# Parametrischer_EQ.net
KiCad netlist of a schematic drawn in Altium Designer
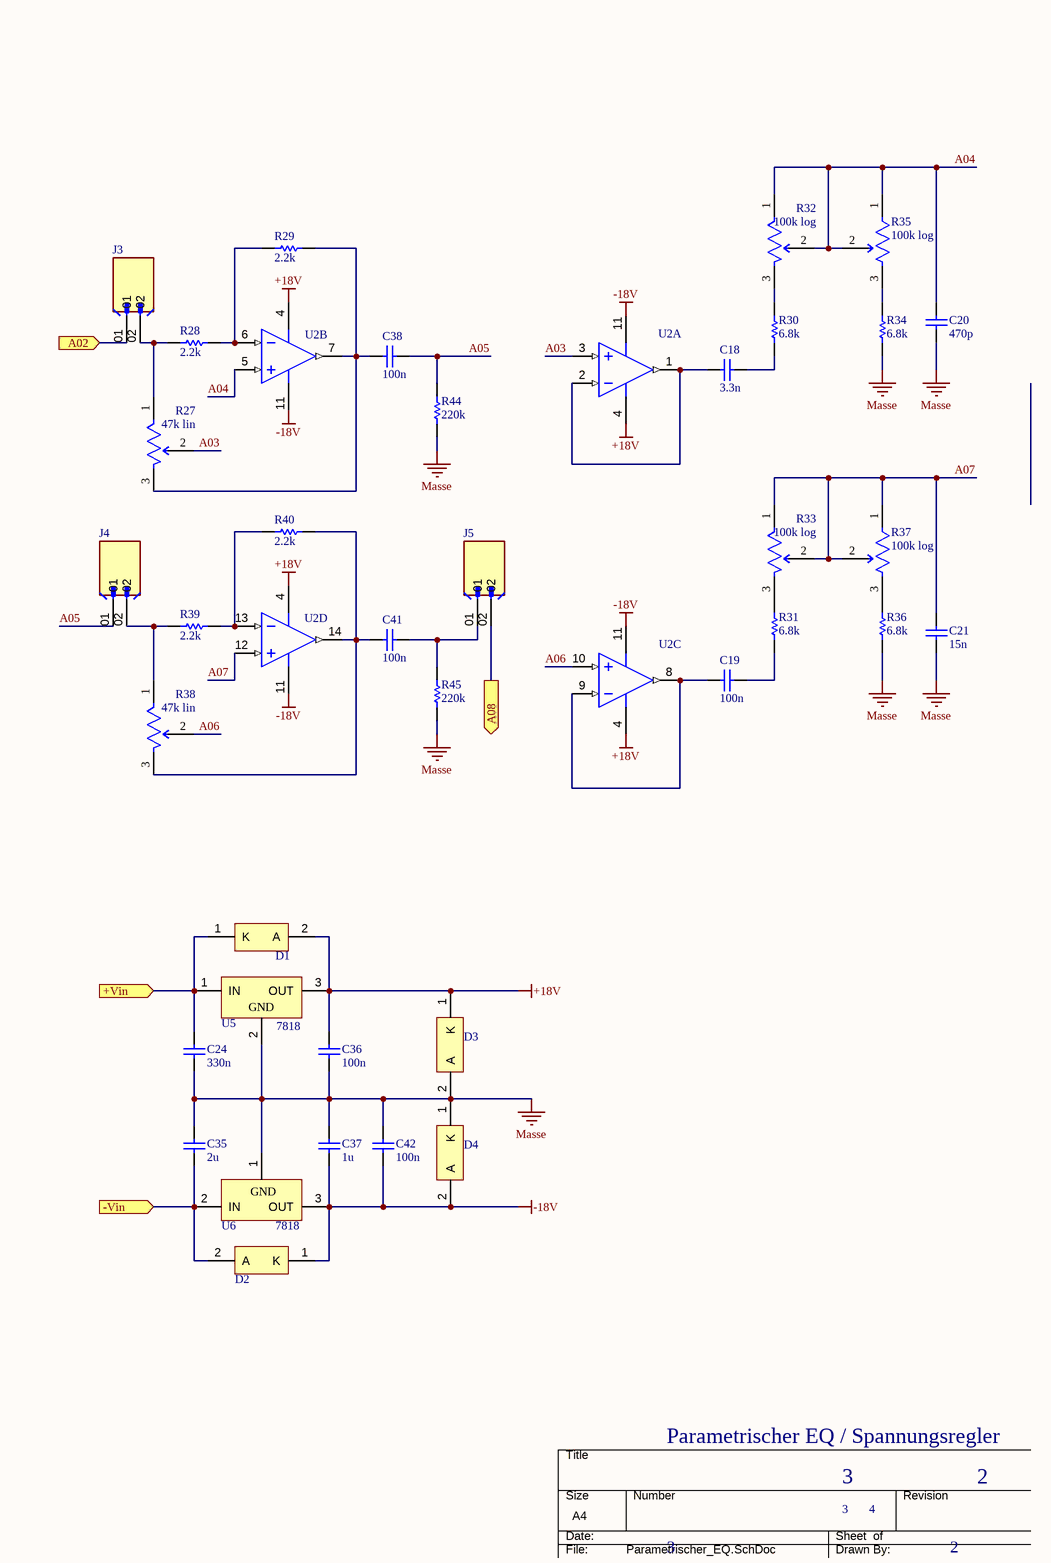
[diagram p0: Parametrischer_EQ.SchDoc]

(export (version "E")
  (design (tool "Eeschema 10.0.6"))
  (components
    (comp (ref "C18")
      (value "3.3n")
      (footprint "0805")
      (description "0805 Kondensator")
      (libsource (lib "Bauteile") (part "0805 Kondensator"))
    )
    (comp (ref "C19")
      (value "100n")
      (footprint "0805")
      (description "0805 Kondensator")
      (libsource (lib "Bauteile") (part "0805 Kondensator"))
    )
    (comp (ref "C20")
      (value "470p")
      (footprint "0805")
      (description "0805 Kondensator")
      (libsource (lib "Bauteile") (part "0805 Kondensator"))
    )
    (comp (ref "C21")
      (value "15n")
      (footprint "0805")
      (description "0805 Kondensator")
      (libsource (lib "Bauteile") (part "0805 Kondensator"))
    )
    (comp (ref "C24")
      (value "330n")
      (footprint "0805")
      (description "0805 Kondensator")
      (libsource (lib "Bauteile") (part "0805 Kondensator"))
    )
    (comp (ref "C35")
      (value "2u")
      (footprint "0805")
      (description "0805 Kondensator")
      (libsource (lib "Bauteile") (part "0805 Kondensator"))
    )
    (comp (ref "C36")
      (value "100n")
      (footprint "0805")
      (description "0805 Kondensator")
      (libsource (lib "Bauteile") (part "0805 Kondensator"))
    )
    (comp (ref "C37")
      (value "1u")
      (footprint "0805")
      (description "0805 Kondensator")
      (libsource (lib "Bauteile") (part "0805 Kondensator"))
    )
    (comp (ref "C38")
      (value "100n")
      (footprint "0805")
      (description "0805 Kondensator")
      (libsource (lib "Bauteile") (part "0805 Kondensator"))
    )
    (comp (ref "C41")
      (value "100n")
      (footprint "0805")
      (description "0805 Kondensator")
      (libsource (lib "Bauteile") (part "0805 Kondensator"))
    )
    (comp (ref "C42")
      (value "100n")
      (footprint "0805")
      (description "0805 Kondensator")
      (libsource (lib "Bauteile") (part "0805 Kondensator"))
    )
    (comp (ref "D1")
      (value "1N4001 Diode")
      (footprint "1N4001 Diode")
      (description "Standard Recovery Rectifier, 2-Pin Axial_Lead, Pb-Free, Bulk Bag")
      (fields (field (name "PARTNUMBER") "1N4001") (field (name "MANUFACTURER") "On Semiconductor"))
      (libsource (lib "") (part "1N4001 Diode_2"))
    )
    (comp (ref "D2")
      (value "1N4001 Diode")
      (footprint "1N4001 Diode")
      (description "Standard Recovery Rectifier, 2-Pin Axial_Lead, Pb-Free, Bulk Bag")
      (fields (field (name "PARTNUMBER") "1N4001") (field (name "MANUFACTURER") "On Semiconductor"))
      (libsource (lib "Bauteile") (part "1N4001 Diode"))
    )
    (comp (ref "D3")
      (value "1N4001 Diode")
      (footprint "1N4001 Diode")
      (description "Standard Recovery Rectifier, 2-Pin Axial_Lead, Pb-Free, Bulk Bag")
      (fields (field (name "PARTNUMBER") "1N4001") (field (name "MANUFACTURER") "On Semiconductor"))
      (libsource (lib "") (part "1N4001 Diode_1"))
    )
    (comp (ref "D4")
      (value "1N4001 Diode")
      (footprint "1N4001 Diode")
      (description "Standard Recovery Rectifier, 2-Pin Axial_Lead, Pb-Free, Bulk Bag")
      (fields (field (name "PARTNUMBER") "1N4001") (field (name "MANUFACTURER") "On Semiconductor"))
      (libsource (lib "") (part "1N4001 Diode_1"))
    )
    (comp (ref "J3")
      (value "Connector x2")
      (footprint "Connector x2")
      (description "Connector Header Through Hole 2 position 0.100 (2.54mm)")
      (fields (field (name "MF") "Wurth Elektronik") (field (name "MP") "61300211121"))
      (libsource (lib "Bauteile") (part "Connector x2"))
    )
    (comp (ref "J4")
      (value "Connector x2")
      (footprint "Connector x2")
      (description "Connector Header Through Hole 2 position 0.100 (2.54mm)")
      (fields (field (name "MF") "Wurth Elektronik") (field (name "MP") "61300211121"))
      (libsource (lib "Bauteile") (part "Connector x2"))
    )
    (comp (ref "J5")
      (value "Connector x2")
      (footprint "Connector x2")
      (description "Connector Header Through Hole 2 position 0.100 (2.54mm)")
      (fields (field (name "MF") "Wurth Elektronik") (field (name "MP") "61300211121"))
      (libsource (lib "Bauteile") (part "Connector x2"))
    )
    (comp (ref "R27")
      (value "47k lin")
      (footprint "Connector x3")
      (description "Potentiometer")
      (libsource (lib "Bauteile") (part "Potentiometer Buchsenleiste"))
    )
    (comp (ref "R28")
      (value "2.2k")
      (footprint "0805")
      (description "0805 Widerstand")
      (libsource (lib "Bauteile") (part "0805 Widerstand"))
    )
    (comp (ref "R29")
      (value "2.2k")
      (footprint "0805")
      (description "0805 Widerstand")
      (libsource (lib "Bauteile") (part "0805 Widerstand"))
    )
    (comp (ref "R30")
      (value "6.8k")
      (footprint "0805")
      (description "0805 Widerstand")
      (libsource (lib "Bauteile") (part "0805 Widerstand"))
    )
    (comp (ref "R31")
      (value "6.8k")
      (footprint "0805")
      (description "0805 Widerstand")
      (libsource (lib "Bauteile") (part "0805 Widerstand"))
    )
    (comp (ref "R32")
      (value "100k log")
      (footprint "Connector x3")
      (description "Potentiometer")
      (libsource (lib "Bauteile") (part "Potentiometer Buchsenleiste"))
    )
    (comp (ref "R33")
      (value "100k log")
      (footprint "Connector x3")
      (description "Potentiometer")
      (libsource (lib "Bauteile") (part "Potentiometer Buchsenleiste"))
    )
    (comp (ref "R34")
      (value "6.8k")
      (footprint "0805")
      (description "0805 Widerstand")
      (libsource (lib "Bauteile") (part "0805 Widerstand"))
    )
    (comp (ref "R35")
      (value "100k log")
      (footprint "Connector x3")
      (description "Potentiometer")
      (libsource (lib "Bauteile") (part "Potentiometer Buchsenleiste"))
    )
    (comp (ref "R36")
      (value "6.8k")
      (footprint "0805")
      (description "0805 Widerstand")
      (libsource (lib "Bauteile") (part "0805 Widerstand"))
    )
    (comp (ref "R37")
      (value "100k log")
      (footprint "Connector x3")
      (description "Potentiometer")
      (libsource (lib "Bauteile") (part "Potentiometer Buchsenleiste"))
    )
    (comp (ref "R38")
      (value "47k lin")
      (footprint "Connector x3")
      (description "Potentiometer")
      (libsource (lib "Bauteile") (part "Potentiometer Buchsenleiste"))
    )
    (comp (ref "R39")
      (value "2.2k")
      (footprint "0805")
      (description "0805 Widerstand")
      (libsource (lib "Bauteile") (part "0805 Widerstand"))
    )
    (comp (ref "R40")
      (value "2.2k")
      (footprint "0805")
      (description "0805 Widerstand")
      (libsource (lib "Bauteile") (part "0805 Widerstand"))
    )
    (comp (ref "R44")
      (value "220k")
      (footprint "0805")
      (description "0805 Widerstand")
      (libsource (lib "Bauteile") (part "0805 Widerstand"))
    )
    (comp (ref "R45")
      (value "220k")
      (footprint "0805")
      (description "0805 Widerstand")
      (libsource (lib "Bauteile") (part "0805 Widerstand"))
    )
    (comp (ref "U2")
      (value "OPA4134UA")
      (footprint "DIP14 IC Socket")
      (fields (field (name "MANUFACTURER") "Texas Instruments"))
      (libsource (lib "Bauteile") (part "SOIC OPA4134UA"))
    )
    (comp (ref "U5")
      (value "7818")
      (footprint "TO220 Spannungsregler 78xx")
      (description "Voltage Regulator, 3-Pin TO-220")
      (libsource (lib "Bauteile") (part "TO 220 Spannungsregler 78xx"))
    )
    (comp (ref "U6")
      (value "7818")
      (footprint "TO220 Spannungsregler 79xx")
      (description "Voltage Regulator, 3-Pin TO-220")
      (libsource (lib "Bauteile") (part "TO 220 Spannungsregler 79xx"))
    )
  )
  (nets
    (net (code "1") (name "+18V") (class "Default")
      (node (ref "C36") (pin "2") (pinfunction "2_2") (pintype "passive"))
      (node (ref "D1") (pin "2") (pinfunction "A_2") (pintype "passive"))
      (node (ref "D3") (pin "1") (pinfunction "K_1") (pintype "passive"))
      (node (ref "U2") (pin "4") (pinfunction "V+_4") (pintype "power_in"))
      (node (ref "U5") (pin "3") (pinfunction "OUT_3") (pintype "power_in"))
    )
    (net (code "2") (name "-18V") (class "Default")
      (node (ref "C37") (pin "2") (pinfunction "2_2") (pintype "passive"))
      (node (ref "C42") (pin "1") (pinfunction "1_1") (pintype "passive"))
      (node (ref "D2") (pin "1") (pinfunction "K_1") (pintype "passive"))
      (node (ref "D4") (pin "2") (pinfunction "A_2") (pintype "passive"))
      (node (ref "U2") (pin "11") (pinfunction "V-_11") (pintype "power_in"))
      (node (ref "U6") (pin "3") (pinfunction "OUT_3") (pintype "power_in"))
    )
    (net (code "3") (name "/+Vin") (class "Default")
      (node (ref "C24") (pin "2") (pinfunction "2_2") (pintype "passive"))
      (node (ref "D1") (pin "1") (pinfunction "K_1") (pintype "passive"))
      (node (ref "U5") (pin "1") (pinfunction "IN_1") (pintype "passive"))
    )
    (net (code "4") (name "/-Vin") (class "Default")
      (node (ref "C35") (pin "2") (pinfunction "2_2") (pintype "passive"))
      (node (ref "D2") (pin "2") (pinfunction "A_2") (pintype "passive"))
      (node (ref "U6") (pin "2") (pinfunction "IN_2") (pintype "passive"))
    )
    (net (code "5") (name "/A02") (class "Default")
      (node (ref "J3") (pin "01") (pinfunction "01_01") (pintype "passive"))
    )
    (net (code "6") (name "/A03") (class "Default")
      (node (ref "R27") (pin "2") (pinfunction "b_2") (pintype "passive"))
      (node (ref "U2") (pin "3") (pinfunction "IN_A+_3") (pintype "input"))
    )
    (net (code "7") (name "/A04") (class "Default")
      (node (ref "C20") (pin "2") (pinfunction "2_2") (pintype "passive"))
      (node (ref "R32") (pin "1") (pinfunction "a_1") (pintype "passive"))
      (node (ref "R32") (pin "2") (pinfunction "b_2") (pintype "passive"))
      (node (ref "R35") (pin "1") (pinfunction "a_1") (pintype "passive"))
      (node (ref "R35") (pin "2") (pinfunction "b_2") (pintype "passive"))
      (node (ref "U2") (pin "5") (pinfunction "IN_B+_5") (pintype "input"))
    )
    (net (code "8") (name "/A05") (class "Default")
      (node (ref "C38") (pin "2") (pinfunction "2_2") (pintype "passive"))
      (node (ref "J4") (pin "01") (pinfunction "01_01") (pintype "passive"))
      (node (ref "R44") (pin "2") (pinfunction "2_2") (pintype "passive"))
    )
    (net (code "9") (name "/A06") (class "Default")
      (node (ref "R38") (pin "2") (pinfunction "b_2") (pintype "passive"))
      (node (ref "U2") (pin "10") (pinfunction "IN_C+_10") (pintype "input"))
    )
    (net (code "10") (name "/A07") (class "Default")
      (node (ref "C21") (pin "1") (pinfunction "1_1") (pintype "passive"))
      (node (ref "R33") (pin "1") (pinfunction "a_1") (pintype "passive"))
      (node (ref "R33") (pin "2") (pinfunction "b_2") (pintype "passive"))
      (node (ref "R37") (pin "1") (pinfunction "a_1") (pintype "passive"))
      (node (ref "R37") (pin "2") (pinfunction "b_2") (pintype "passive"))
      (node (ref "U2") (pin "12") (pinfunction "IN_D+_12") (pintype "input"))
    )
    (net (code "11") (name "/A08") (class "Default")
      (node (ref "J5") (pin "02") (pinfunction "02_02") (pintype "passive"))
    )
    (net (code "12") (name "Masse") (class "Default")
      (node (ref "C20") (pin "1") (pinfunction "1_1") (pintype "passive"))
      (node (ref "C21") (pin "2") (pinfunction "2_2") (pintype "passive"))
      (node (ref "C24") (pin "1") (pinfunction "1_1") (pintype "passive"))
      (node (ref "C35") (pin "1") (pinfunction "1_1") (pintype "passive"))
      (node (ref "C36") (pin "1") (pinfunction "1_1") (pintype "passive"))
      (node (ref "C37") (pin "1") (pinfunction "1_1") (pintype "passive"))
      (node (ref "C42") (pin "2") (pinfunction "2_2") (pintype "passive"))
      (node (ref "D3") (pin "2") (pinfunction "A_2") (pintype "passive"))
      (node (ref "D4") (pin "1") (pinfunction "K_1") (pintype "passive"))
      (node (ref "R34") (pin "1") (pinfunction "1_1") (pintype "passive"))
      (node (ref "R36") (pin "2") (pinfunction "2_2") (pintype "passive"))
      (node (ref "R44") (pin "1") (pinfunction "1_1") (pintype "passive"))
      (node (ref "R45") (pin "1") (pinfunction "1_1") (pintype "passive"))
      (node (ref "U5") (pin "2") (pinfunction "GND_2") (pintype "power_in"))
      (node (ref "U6") (pin "1") (pinfunction "GND_1") (pintype "power_in"))
    )
    (net (code "13") (name "Net-(C18-Pad2)") (class "Default")
      (node (ref "C18") (pin "2") (pinfunction "2_2") (pintype "passive"))
      (node (ref "R30") (pin "1") (pinfunction "1_1") (pintype "passive"))
    )
    (net (code "14") (name "Net-(C19-Pad1)") (class "Default")
      (node (ref "C19") (pin "1") (pinfunction "1_1") (pintype "passive"))
      (node (ref "R31") (pin "2") (pinfunction "2_2") (pintype "passive"))
    )
    (net (code "15") (name "Net-(C41-Pad2)") (class "Default")
      (node (ref "C41") (pin "2") (pinfunction "2_2") (pintype "passive"))
      (node (ref "J5") (pin "01") (pinfunction "01_01") (pintype "passive"))
      (node (ref "R45") (pin "2") (pinfunction "2_2") (pintype "passive"))
    )
    (net (code "16") (name "Net-(R27-a)") (class "Default")
      (node (ref "J3") (pin "02") (pinfunction "02_02") (pintype "passive"))
      (node (ref "R27") (pin "1") (pinfunction "a_1") (pintype "passive"))
      (node (ref "R28") (pin "1") (pinfunction "1_1") (pintype "passive"))
    )
    (net (code "17") (name "Net-(R27-c)") (class "Default")
      (node (ref "C38") (pin "1") (pinfunction "1_1") (pintype "passive"))
      (node (ref "R27") (pin "3") (pinfunction "c_3") (pintype "passive"))
      (node (ref "R29") (pin "2") (pinfunction "2_2") (pintype "passive"))
      (node (ref "U2") (pin "7") (pinfunction "OUT_B_7") (pintype "output"))
    )
    (net (code "18") (name "Net-(R32-c)") (class "Default")
      (node (ref "R30") (pin "2") (pinfunction "2_2") (pintype "passive"))
      (node (ref "R32") (pin "3") (pinfunction "c_3") (pintype "passive"))
    )
    (net (code "19") (name "Net-(R33-c)") (class "Default")
      (node (ref "R31") (pin "1") (pinfunction "1_1") (pintype "passive"))
      (node (ref "R33") (pin "3") (pinfunction "c_3") (pintype "passive"))
    )
    (net (code "20") (name "Net-(R35-c)") (class "Default")
      (node (ref "R34") (pin "2") (pinfunction "2_2") (pintype "passive"))
      (node (ref "R35") (pin "3") (pinfunction "c_3") (pintype "passive"))
    )
    (net (code "21") (name "Net-(R37-c)") (class "Default")
      (node (ref "R36") (pin "1") (pinfunction "1_1") (pintype "passive"))
      (node (ref "R37") (pin "3") (pinfunction "c_3") (pintype "passive"))
    )
    (net (code "22") (name "Net-(R38-a)") (class "Default")
      (node (ref "J4") (pin "02") (pinfunction "02_02") (pintype "passive"))
      (node (ref "R38") (pin "1") (pinfunction "a_1") (pintype "passive"))
      (node (ref "R39") (pin "1") (pinfunction "1_1") (pintype "passive"))
    )
    (net (code "23") (name "Net-(R38-c)") (class "Default")
      (node (ref "C41") (pin "1") (pinfunction "1_1") (pintype "passive"))
      (node (ref "R38") (pin "3") (pinfunction "c_3") (pintype "passive"))
      (node (ref "R40") (pin "2") (pinfunction "2_2") (pintype "passive"))
      (node (ref "U2") (pin "14") (pinfunction "OUT_D_14") (pintype "output"))
    )
    (net (code "24") (name "Net-(U2A-IN_A-)") (class "Default")
      (node (ref "C18") (pin "1") (pinfunction "1_1") (pintype "passive"))
      (node (ref "U2") (pin "1") (pinfunction "OUT_A_1") (pintype "output"))
      (node (ref "U2") (pin "2") (pinfunction "IN_A-_2") (pintype "input"))
    )
    (net (code "25") (name "Net-(U2B-IN_B-)") (class "Default")
      (node (ref "R28") (pin "2") (pinfunction "2_2") (pintype "passive"))
      (node (ref "R29") (pin "1") (pinfunction "1_1") (pintype "passive"))
      (node (ref "U2") (pin "6") (pinfunction "IN_B-_6") (pintype "input"))
    )
    (net (code "26") (name "Net-(U2C-IN_C-)") (class "Default")
      (node (ref "C19") (pin "2") (pinfunction "2_2") (pintype "passive"))
      (node (ref "U2") (pin "8") (pinfunction "OUT_C_8") (pintype "output"))
      (node (ref "U2") (pin "9") (pinfunction "IN_C-_9") (pintype "input"))
    )
    (net (code "27") (name "Net-(U2D-IN_D-)") (class "Default")
      (node (ref "R39") (pin "2") (pinfunction "2_2") (pintype "passive"))
      (node (ref "R40") (pin "1") (pinfunction "1_1") (pintype "passive"))
      (node (ref "U2") (pin "13") (pinfunction "IN_D-_13") (pintype "input"))
    )
  )
)
